# Funkboard_v1.net
KiCad netlist of a schematic drawn in EAGLE
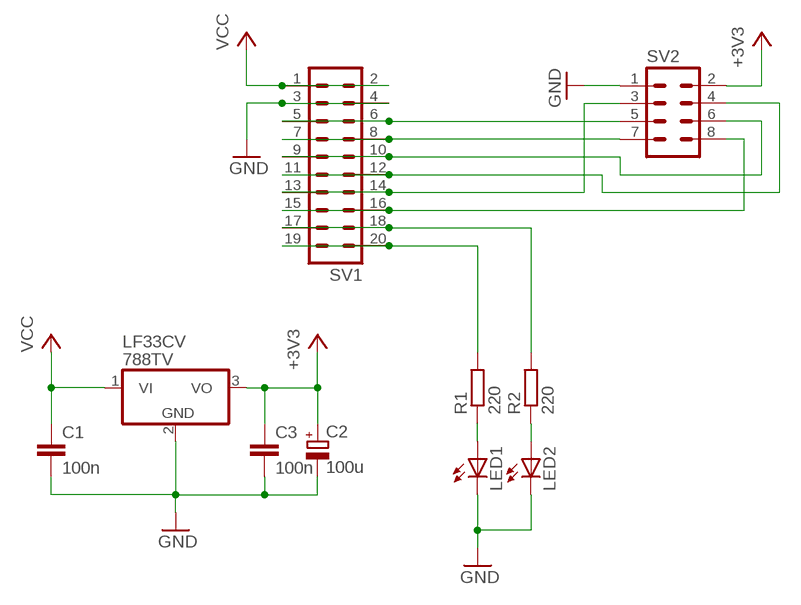
[diagram p0: schematic, sheet 1]

(export (version "E")
  (design (tool "Eeschema 10.0.6"))
  (components
    (comp (ref "C1")
      (value "100n")
      (footprint "eagle-import:C025-025X050")
      (libsource (lib "eagle-import") (part "C-EU025-025X050"))
    )
    (comp (ref "C2")
      (value "100u")
      (footprint "eagle-import:E2,5-6")
      (libsource (lib "eagle-import") (part "CPOL-EUE2.5-6"))
    )
    (comp (ref "C3")
      (value "100n")
      (footprint "eagle-import:C025-025X050")
      (libsource (lib "eagle-import") (part "C-EU025-025X050"))
    )
    (comp (ref "LED1")
      (value "LED3MM")
      (footprint "eagle-import:LED3MM")
      (libsource (lib "eagle-import") (part "LED3MM"))
    )
    (comp (ref "LED2")
      (value "LED3MM")
      (footprint "eagle-import:LED3MM")
      (libsource (lib "eagle-import") (part "LED3MM"))
    )
    (comp (ref "LF33CV")
      (value "788TV")
      (footprint "eagle-import:TO220V")
      (libsource (lib "eagle-import") (part "78TV8"))
    )
    (comp (ref "R1")
      (value "220")
      (footprint "eagle-import:0204V")
      (libsource (lib "eagle-import") (part "R-EU_0204/2V"))
    )
    (comp (ref "R2")
      (value "220")
      (footprint "eagle-import:0204V")
      (libsource (lib "eagle-import") (part "R-EU_0204/2V"))
    )
    (comp (ref "SV1")
      (value "MA10-2W")
      (footprint "eagle-import:MA10-2W")
      (libsource (lib "eagle-import") (part "MA10-2W"))
    )
    (comp (ref "SV2")
      (value "MA04-2")
      (footprint "eagle-import:MA04-2")
      (libsource (lib "eagle-import") (part "MA04-2"))
    )
  )
  (nets
    (net (code "1") (name "+3V3") (class "Default")
      (node (ref "C2") (pin "+") (pinfunction "+_+") (pintype "passive"))
      (node (ref "C3") (pin "1") (pinfunction "1_1") (pintype "passive"))
      (node (ref "LF33CV") (pin "3") (pinfunction "VO_3") (pintype "passive"))
      (node (ref "SV2") (pin "2") (pinfunction "2_2") (pintype "passive"))
    )
    (net (code "2") (name "GND") (class "Default")
      (node (ref "C1") (pin "2") (pinfunction "2_2") (pintype "passive"))
      (node (ref "C2") (pin "-") (pinfunction "-_-") (pintype "passive"))
      (node (ref "C3") (pin "2") (pinfunction "2_2") (pintype "passive"))
      (node (ref "LED1") (pin "K") (pinfunction "C_K") (pintype "passive"))
      (node (ref "LED2") (pin "K") (pinfunction "C_K") (pintype "passive"))
      (node (ref "LF33CV") (pin "2") (pinfunction "GND_2") (pintype "passive"))
      (node (ref "SV1") (pin "3") (pinfunction "3_3") (pintype "passive"))
      (node (ref "SV1") (pin "4") (pinfunction "4_4") (pintype "passive"))
      (node (ref "SV2") (pin "1") (pinfunction "1_1") (pintype "passive"))
    )
    (net (code "3") (name "Net-(LED1-PadA)") (class "Default")
      (node (ref "LED1") (pin "A") (pinfunction "A_A") (pintype "passive"))
      (node (ref "R1") (pin "1") (pinfunction "1_1") (pintype "passive"))
    )
    (net (code "4") (name "Net-(LED2-PadA)") (class "Default")
      (node (ref "LED2") (pin "A") (pinfunction "A_A") (pintype "passive"))
      (node (ref "R2") (pin "1") (pinfunction "1_1") (pintype "passive"))
    )
    (net (code "5") (name "Net-(R1-Pad2)") (class "Default")
      (node (ref "R1") (pin "2") (pinfunction "2_2") (pintype "passive"))
      (node (ref "SV1") (pin "19") (pinfunction "19_19") (pintype "passive"))
      (node (ref "SV1") (pin "20") (pinfunction "20_20") (pintype "passive"))
    )
    (net (code "6") (name "Net-(R2-Pad2)") (class "Default")
      (node (ref "R2") (pin "2") (pinfunction "2_2") (pintype "passive"))
      (node (ref "SV1") (pin "17") (pinfunction "17_17") (pintype "passive"))
      (node (ref "SV1") (pin "18") (pinfunction "18_18") (pintype "passive"))
    )
    (net (code "7") (name "Net-(SV1-Pad5)") (class "Default")
      (node (ref "SV1") (pin "5") (pinfunction "5_5") (pintype "passive"))
      (node (ref "SV1") (pin "6") (pinfunction "6_6") (pintype "passive"))
      (node (ref "SV2") (pin "5") (pinfunction "5_5") (pintype "passive"))
    )
    (net (code "8") (name "Net-(SV1-Pad7)") (class "Default")
      (node (ref "SV1") (pin "7") (pinfunction "7_7") (pintype "passive"))
      (node (ref "SV1") (pin "8") (pinfunction "8_8") (pintype "passive"))
      (node (ref "SV2") (pin "7") (pinfunction "7_7") (pintype "passive"))
    )
    (net (code "9") (name "Net-(SV1-Pad10)") (class "Default")
      (node (ref "SV1") (pin "10") (pinfunction "10_10") (pintype "passive"))
      (node (ref "SV1") (pin "9") (pinfunction "9_9") (pintype "passive"))
      (node (ref "SV2") (pin "6") (pinfunction "6_6") (pintype "passive"))
    )
    (net (code "10") (name "Net-(SV1-Pad11)") (class "Default")
      (node (ref "SV1") (pin "11") (pinfunction "11_11") (pintype "passive"))
      (node (ref "SV1") (pin "12") (pinfunction "12_12") (pintype "passive"))
      (node (ref "SV2") (pin "4") (pinfunction "4_4") (pintype "passive"))
    )
    (net (code "11") (name "Net-(SV1-Pad13)") (class "Default")
      (node (ref "SV1") (pin "13") (pinfunction "13_13") (pintype "passive"))
      (node (ref "SV1") (pin "14") (pinfunction "14_14") (pintype "passive"))
      (node (ref "SV2") (pin "3") (pinfunction "3_3") (pintype "passive"))
    )
    (net (code "12") (name "Net-(SV1-Pad15)") (class "Default")
      (node (ref "SV1") (pin "15") (pinfunction "15_15") (pintype "passive"))
      (node (ref "SV1") (pin "16") (pinfunction "16_16") (pintype "passive"))
      (node (ref "SV2") (pin "8") (pinfunction "8_8") (pintype "passive"))
    )
    (net (code "13") (name "VCC") (class "Default")
      (node (ref "C1") (pin "1") (pinfunction "1_1") (pintype "passive"))
      (node (ref "LF33CV") (pin "1") (pinfunction "VI_1") (pintype "input"))
      (node (ref "SV1") (pin "1") (pinfunction "1_1") (pintype "passive"))
      (node (ref "SV1") (pin "2") (pinfunction "2_2") (pintype "passive"))
    )
  )
)
